# BlazeIt.net
KiCad netlist of a schematic drawn in EAGLE
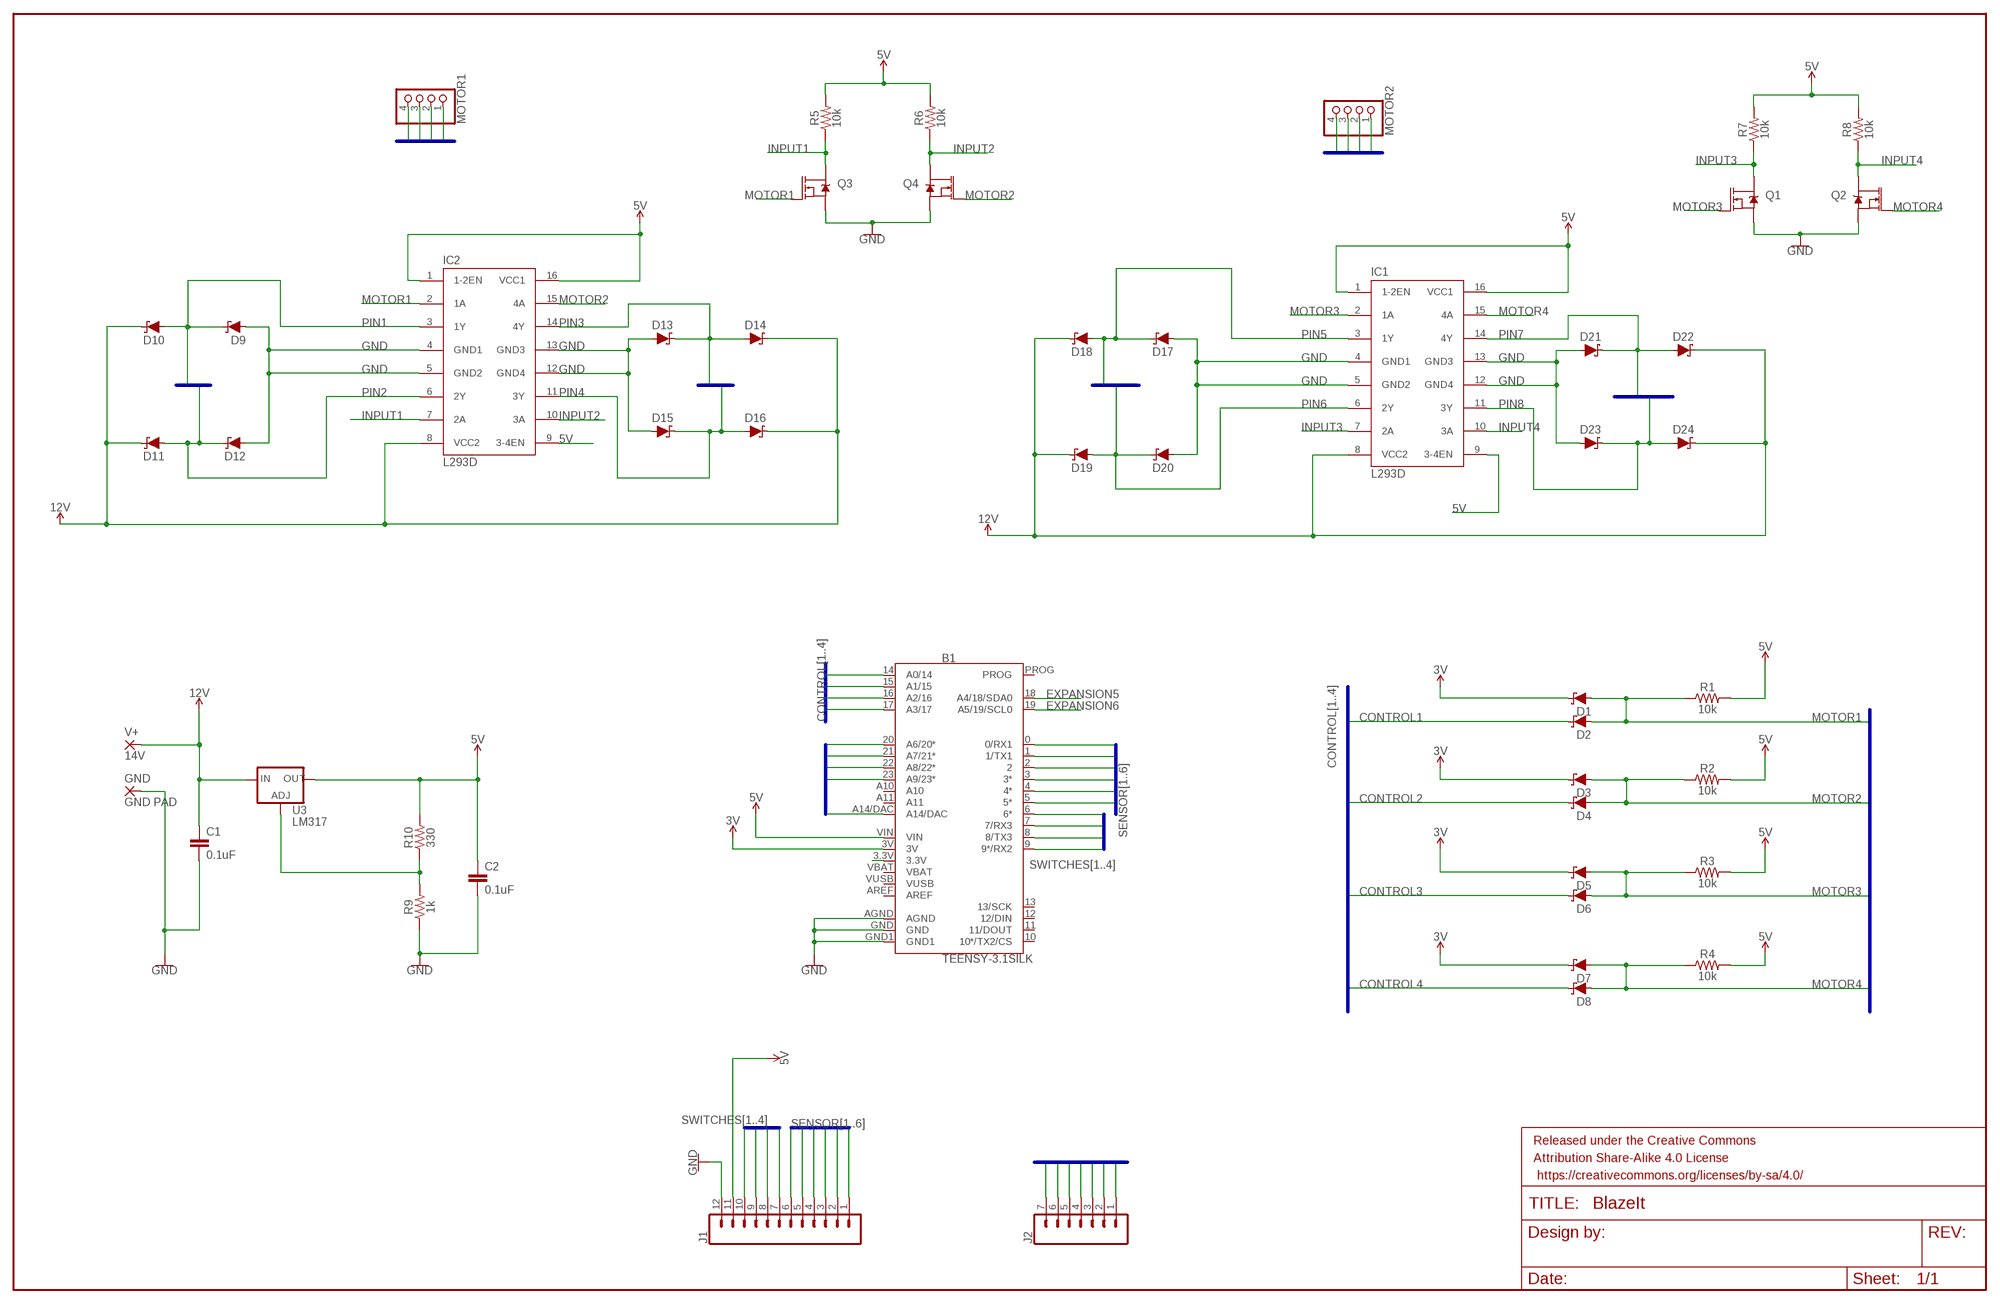
[diagram p0: schematic, sheet 1]

(export (version "E")
  (design (tool "Eeschema 10.0.6"))
  (components
    (comp (ref "B1")
      (value "TEENSY-3.1SILK")
      (footprint "eagle-import:TEENSY-3.1")
      (libsource (lib "eagle-import") (part "TEENSY-3.1SILK"))
    )
    (comp (ref "C1")
      (value "0.1uF")
      (footprint "eagle-import:0603")
      (libsource (lib "eagle-import") (part "0.1UF-0603-25V-5%"))
    )
    (comp (ref "C2")
      (value "0.1uF")
      (footprint "eagle-import:0603")
      (libsource (lib "eagle-import") (part "0.1UF-0603-25V-5%"))
    )
    (comp (ref "D1")
      (value "DIODE-SCHOTTKY-PMEG4005EJ")
      (footprint "eagle-import:SOD-323")
      (libsource (lib "eagle-import") (part "DIODE-SCHOTTKY-PMEG4005EJ"))
    )
    (comp (ref "D2")
      (value "DIODE-SCHOTTKY-PMEG4005EJ")
      (footprint "eagle-import:SOD-323")
      (libsource (lib "eagle-import") (part "DIODE-SCHOTTKY-PMEG4005EJ"))
    )
    (comp (ref "D3")
      (value "DIODE-SCHOTTKY-PMEG4005EJ")
      (footprint "eagle-import:SOD-323")
      (libsource (lib "eagle-import") (part "DIODE-SCHOTTKY-PMEG4005EJ"))
    )
    (comp (ref "D4")
      (value "DIODE-SCHOTTKY-PMEG4005EJ")
      (footprint "eagle-import:SOD-323")
      (libsource (lib "eagle-import") (part "DIODE-SCHOTTKY-PMEG4005EJ"))
    )
    (comp (ref "D5")
      (value "DIODE-SCHOTTKY-PMEG4005EJ")
      (footprint "eagle-import:SOD-323")
      (libsource (lib "eagle-import") (part "DIODE-SCHOTTKY-PMEG4005EJ"))
    )
    (comp (ref "D6")
      (value "DIODE-SCHOTTKY-PMEG4005EJ")
      (footprint "eagle-import:SOD-323")
      (libsource (lib "eagle-import") (part "DIODE-SCHOTTKY-PMEG4005EJ"))
    )
    (comp (ref "D7")
      (value "DIODE-SCHOTTKY-PMEG4005EJ")
      (footprint "eagle-import:SOD-323")
      (libsource (lib "eagle-import") (part "DIODE-SCHOTTKY-PMEG4005EJ"))
    )
    (comp (ref "D8")
      (value "DIODE-SCHOTTKY-PMEG4005EJ")
      (footprint "eagle-import:SOD-323")
      (libsource (lib "eagle-import") (part "DIODE-SCHOTTKY-PMEG4005EJ"))
    )
    (comp (ref "D9")
      (value "DIODE-SCHOTTKY-PMEG4005EJ")
      (footprint "eagle-import:SOD-323")
      (libsource (lib "eagle-import") (part "DIODE-SCHOTTKY-PMEG4005EJ"))
    )
    (comp (ref "D10")
      (value "DIODE-SCHOTTKY-PMEG4005EJ")
      (footprint "eagle-import:SOD-323")
      (libsource (lib "eagle-import") (part "DIODE-SCHOTTKY-PMEG4005EJ"))
    )
    (comp (ref "D11")
      (value "DIODE-SCHOTTKY-PMEG4005EJ")
      (footprint "eagle-import:SOD-323")
      (libsource (lib "eagle-import") (part "DIODE-SCHOTTKY-PMEG4005EJ"))
    )
    (comp (ref "D12")
      (value "DIODE-SCHOTTKY-PMEG4005EJ")
      (footprint "eagle-import:SOD-323")
      (libsource (lib "eagle-import") (part "DIODE-SCHOTTKY-PMEG4005EJ"))
    )
    (comp (ref "D13")
      (value "DIODE-SCHOTTKY-PMEG4005EJ")
      (footprint "eagle-import:SOD-323")
      (libsource (lib "eagle-import") (part "DIODE-SCHOTTKY-PMEG4005EJ"))
    )
    (comp (ref "D14")
      (value "DIODE-SCHOTTKY-PMEG4005EJ")
      (footprint "eagle-import:SOD-323")
      (libsource (lib "eagle-import") (part "DIODE-SCHOTTKY-PMEG4005EJ"))
    )
    (comp (ref "D15")
      (value "DIODE-SCHOTTKY-PMEG4005EJ")
      (footprint "eagle-import:SOD-323")
      (libsource (lib "eagle-import") (part "DIODE-SCHOTTKY-PMEG4005EJ"))
    )
    (comp (ref "D16")
      (value "DIODE-SCHOTTKY-PMEG4005EJ")
      (footprint "eagle-import:SOD-323")
      (libsource (lib "eagle-import") (part "DIODE-SCHOTTKY-PMEG4005EJ"))
    )
    (comp (ref "D17")
      (value "DIODE-SCHOTTKY-PMEG4005EJ")
      (footprint "eagle-import:SOD-323")
      (libsource (lib "eagle-import") (part "DIODE-SCHOTTKY-PMEG4005EJ"))
    )
    (comp (ref "D18")
      (value "DIODE-SCHOTTKY-PMEG4005EJ")
      (footprint "eagle-import:SOD-323")
      (libsource (lib "eagle-import") (part "DIODE-SCHOTTKY-PMEG4005EJ"))
    )
    (comp (ref "D19")
      (value "DIODE-SCHOTTKY-PMEG4005EJ")
      (footprint "eagle-import:SOD-323")
      (libsource (lib "eagle-import") (part "DIODE-SCHOTTKY-PMEG4005EJ"))
    )
    (comp (ref "D20")
      (value "DIODE-SCHOTTKY-PMEG4005EJ")
      (footprint "eagle-import:SOD-323")
      (libsource (lib "eagle-import") (part "DIODE-SCHOTTKY-PMEG4005EJ"))
    )
    (comp (ref "D21")
      (value "DIODE-SCHOTTKY-PMEG4005EJ")
      (footprint "eagle-import:SOD-323")
      (libsource (lib "eagle-import") (part "DIODE-SCHOTTKY-PMEG4005EJ"))
    )
    (comp (ref "D22")
      (value "DIODE-SCHOTTKY-PMEG4005EJ")
      (footprint "eagle-import:SOD-323")
      (libsource (lib "eagle-import") (part "DIODE-SCHOTTKY-PMEG4005EJ"))
    )
    (comp (ref "D23")
      (value "DIODE-SCHOTTKY-PMEG4005EJ")
      (footprint "eagle-import:SOD-323")
      (libsource (lib "eagle-import") (part "DIODE-SCHOTTKY-PMEG4005EJ"))
    )
    (comp (ref "D24")
      (value "DIODE-SCHOTTKY-PMEG4005EJ")
      (footprint "eagle-import:SOD-323")
      (libsource (lib "eagle-import") (part "DIODE-SCHOTTKY-PMEG4005EJ"))
    )
    (comp (ref "FRAME1")
      (value "FRAME-LEDGER")
      (footprint "eagle-import:CREATIVE_COMMONS")
      (libsource (lib "eagle-import") (part "FRAME-LEDGER"))
    )
    (comp (ref "GND")
      (value "GND PAD")
      (footprint "eagle-import:SMD2,54-5,08")
      (libsource (lib "eagle-import") (part "WIREPADSMD2,54-5,08"))
    )
    (comp (ref "IC1")
      (value "L293D")
      (footprint "eagle-import:DIL16")
      (libsource (lib "eagle-import") (part "L293D"))
    )
    (comp (ref "IC2")
      (value "L293D")
      (footprint "eagle-import:DIL16")
      (libsource (lib "eagle-import") (part "L293D"))
    )
    (comp (ref "J1")
      (value "CONN_12")
      (footprint "eagle-import:1X12")
      (libsource (lib "eagle-import") (part "CONN_12"))
    )
    (comp (ref "J2")
      (value "CONN_07LOCK")
      (footprint "eagle-import:1X07_LOCK")
      (libsource (lib "eagle-import") (part "CONN_07LOCK"))
    )
    (comp (ref "MOTOR1")
      (value "PINHD-1X4")
      (footprint "eagle-import:1X04")
      (libsource (lib "eagle-import") (part "PINHD-1X4"))
    )
    (comp (ref "MOTOR2")
      (value "PINHD-1X4")
      (footprint "eagle-import:1X04")
      (libsource (lib "eagle-import") (part "PINHD-1X4"))
    )
    (comp (ref "Q1")
      (value "MOSFET-NCH-2N7002PW")
      (footprint "eagle-import:SOT323")
      (libsource (lib "eagle-import") (part "MOSFET-NCH-2N7002PW"))
    )
    (comp (ref "Q2")
      (value "MOSFET-NCH-2N7002PW")
      (footprint "eagle-import:SOT323")
      (libsource (lib "eagle-import") (part "MOSFET-NCH-2N7002PW"))
    )
    (comp (ref "Q3")
      (value "MOSFET-NCH-2N7002PW")
      (footprint "eagle-import:SOT323")
      (libsource (lib "eagle-import") (part "MOSFET-NCH-2N7002PW"))
    )
    (comp (ref "Q4")
      (value "MOSFET-NCH-2N7002PW")
      (footprint "eagle-import:SOT323")
      (libsource (lib "eagle-import") (part "MOSFET-NCH-2N7002PW"))
    )
    (comp (ref "R1")
      (value "10k")
      (footprint "eagle-import:0603")
      (libsource (lib "eagle-import") (part "10KOHM-0603-1/10W-1%"))
    )
    (comp (ref "R2")
      (value "10k")
      (footprint "eagle-import:0603")
      (libsource (lib "eagle-import") (part "10KOHM-0603-1/10W-1%"))
    )
    (comp (ref "R3")
      (value "10k")
      (footprint "eagle-import:0603")
      (libsource (lib "eagle-import") (part "10KOHM-0603-1/10W-1%"))
    )
    (comp (ref "R4")
      (value "10k")
      (footprint "eagle-import:0603")
      (libsource (lib "eagle-import") (part "10KOHM-0603-1/10W-1%"))
    )
    (comp (ref "R5")
      (value "10k")
      (footprint "eagle-import:0603")
      (libsource (lib "eagle-import") (part "10KOHM-0603-1/10W-1%"))
    )
    (comp (ref "R6")
      (value "10k")
      (footprint "eagle-import:0603")
      (libsource (lib "eagle-import") (part "10KOHM-0603-1/10W-1%"))
    )
    (comp (ref "R7")
      (value "10k")
      (footprint "eagle-import:0603")
      (libsource (lib "eagle-import") (part "10KOHM-0603-1/10W-1%"))
    )
    (comp (ref "R8")
      (value "10k")
      (footprint "eagle-import:0603")
      (libsource (lib "eagle-import") (part "10KOHM-0603-1/10W-1%"))
    )
    (comp (ref "R9")
      (value "1k")
      (footprint "eagle-import:0603")
      (libsource (lib "eagle-import") (part "1KOHM-0603-1/10W-1%"))
    )
    (comp (ref "R10")
      (value "330")
      (footprint "eagle-import:0603")
      (libsource (lib "eagle-import") (part "3.3KOHM-0603-1/10W-1%"))
    )
    (comp (ref "U3")
      (value "LM317")
      (footprint "eagle-import:TO220-ADJ")
      (libsource (lib "eagle-import") (part "V_REG_317SINK"))
    )
    (comp (ref "V+")
      (value "14V")
      (footprint "eagle-import:SMD2,54-5,08")
      (libsource (lib "eagle-import") (part "WIREPADSMD2,54-5,08"))
    )
  )
  (nets
    (net (code "5") (name "3.3V") (class "Default")
      (node (ref "B1") (pin "3V") (pinfunction "3V_3V") (pintype "power_in"))
      (node (ref "D1") (pin "C") (pinfunction "C_C") (pintype "passive"))
      (node (ref "D3") (pin "C") (pinfunction "C_C") (pintype "passive"))
      (node (ref "D5") (pin "C") (pinfunction "C_C") (pintype "passive"))
      (node (ref "D7") (pin "C") (pinfunction "C_C") (pintype "passive"))
    )
    (net (code "6") (name "5V") (class "Default")
      (node (ref "B1") (pin "VIN") (pinfunction "VIN_VIN") (pintype "power_in"))
      (node (ref "C2") (pin "1") (pinfunction "1_1") (pintype "passive"))
      (node (ref "IC1") (pin "1") (pinfunction "1-2EN_1") (pintype "input"))
      (node (ref "IC1") (pin "16") (pinfunction "VCC1_16") (pintype "power_in"))
      (node (ref "IC1") (pin "9") (pinfunction "3-4EN_9") (pintype "input"))
      (node (ref "IC2") (pin "1") (pinfunction "1-2EN_1") (pintype "input"))
      (node (ref "IC2") (pin "16") (pinfunction "VCC1_16") (pintype "power_in"))
      (node (ref "IC2") (pin "9") (pinfunction "3-4EN_9") (pintype "input"))
      (node (ref "J1") (pin "11") (pinfunction "11_11") (pintype "passive"))
      (node (ref "R1") (pin "2") (pinfunction "2_2") (pintype "passive"))
      (node (ref "R10") (pin "2") (pinfunction "2_2") (pintype "passive"))
      (node (ref "R2") (pin "2") (pinfunction "2_2") (pintype "passive"))
      (node (ref "R3") (pin "2") (pinfunction "2_2") (pintype "passive"))
      (node (ref "R4") (pin "2") (pinfunction "2_2") (pintype "passive"))
      (node (ref "R5") (pin "2") (pinfunction "2_2") (pintype "passive"))
      (node (ref "R6") (pin "2") (pinfunction "2_2") (pintype "passive"))
      (node (ref "R7") (pin "2") (pinfunction "2_2") (pintype "passive"))
      (node (ref "R8") (pin "2") (pinfunction "2_2") (pintype "passive"))
      (node (ref "U3") (pin "OUT") (pinfunction "OUT_OUT") (pintype "output"))
    )
    (net (code "7") (name "12V") (class "Default")
      (node (ref "C1") (pin "1") (pinfunction "1_1") (pintype "passive"))
      (node (ref "D10") (pin "C") (pinfunction "C_C") (pintype "passive"))
      (node (ref "D11") (pin "C") (pinfunction "C_C") (pintype "passive"))
      (node (ref "D14") (pin "C") (pinfunction "C_C") (pintype "passive"))
      (node (ref "D16") (pin "C") (pinfunction "C_C") (pintype "passive"))
      (node (ref "D18") (pin "C") (pinfunction "C_C") (pintype "passive"))
      (node (ref "D19") (pin "C") (pinfunction "C_C") (pintype "passive"))
      (node (ref "D22") (pin "C") (pinfunction "C_C") (pintype "passive"))
      (node (ref "D24") (pin "C") (pinfunction "C_C") (pintype "passive"))
      (node (ref "IC1") (pin "8") (pinfunction "VCC2_8") (pintype "power_in"))
      (node (ref "IC2") (pin "8") (pinfunction "VCC2_8") (pintype "power_in"))
      (node (ref "U3") (pin "IN") (pinfunction "IN_IN") (pintype "input"))
      (node (ref "V+") (pin "1") (pinfunction "P_1") (pintype "passive"))
    )
    (net (code "8") (name "CONTROL1") (class "Default")
      (node (ref "B1") (pin "17") (pinfunction "A3/17_17") (pintype "bidirectional"))
      (node (ref "D2") (pin "C") (pinfunction "C_C") (pintype "passive"))
    )
    (net (code "9") (name "CONTROL2") (class "Default")
      (node (ref "B1") (pin "16") (pinfunction "A2/16_16") (pintype "bidirectional"))
      (node (ref "D4") (pin "C") (pinfunction "C_C") (pintype "passive"))
    )
    (net (code "10") (name "CONTROL3") (class "Default")
      (node (ref "B1") (pin "15") (pinfunction "A1/15_15") (pintype "bidirectional"))
      (node (ref "D6") (pin "C") (pinfunction "C_C") (pintype "passive"))
    )
    (net (code "11") (name "CONTROL4") (class "Default")
      (node (ref "B1") (pin "14") (pinfunction "A0/14_14") (pintype "bidirectional"))
      (node (ref "D8") (pin "C") (pinfunction "C_C") (pintype "passive"))
    )
    (net (code "12") (name "EXPANSION1") (class "Default")
      (node (ref "B1") (pin "20") (pinfunction "A6/20*_20") (pintype "bidirectional"))
      (node (ref "J2") (pin "1") (pinfunction "1_1") (pintype "passive"))
    )
    (net (code "13") (name "EXPANSION2") (class "Default")
      (node (ref "B1") (pin "21") (pinfunction "A7/21*_21") (pintype "bidirectional"))
      (node (ref "J2") (pin "2") (pinfunction "2_2") (pintype "passive"))
    )
    (net (code "14") (name "EXPANSION3") (class "Default")
      (node (ref "B1") (pin "22") (pinfunction "A8/22*_22") (pintype "bidirectional"))
      (node (ref "J2") (pin "3") (pinfunction "3_3") (pintype "passive"))
    )
    (net (code "15") (name "EXPANSION4") (class "Default")
      (node (ref "B1") (pin "23") (pinfunction "A9/23*_23") (pintype "bidirectional"))
      (node (ref "J2") (pin "4") (pinfunction "4_4") (pintype "passive"))
    )
    (net (code "16") (name "EXPANSION5") (class "Default")
      (node (ref "B1") (pin "18") (pinfunction "A4/18/SDA0_18") (pintype "bidirectional"))
      (node (ref "J2") (pin "5") (pinfunction "5_5") (pintype "passive"))
    )
    (net (code "17") (name "EXPANSION6") (class "Default")
      (node (ref "B1") (pin "19") (pinfunction "A5/19/SCL0_19") (pintype "bidirectional"))
      (node (ref "J2") (pin "6") (pinfunction "6_6") (pintype "passive"))
    )
    (net (code "18") (name "EXPANSION7") (class "Default")
      (node (ref "B1") (pin "A14/DAC") (pinfunction "A14/DAC_A14/DAC") (pintype "bidirectional"))
      (node (ref "J2") (pin "7") (pinfunction "7_7") (pintype "passive"))
    )
    (net (code "19") (name "GND") (class "Default")
      (node (ref "B1") (pin "AGND") (pinfunction "AGND_AGND") (pintype "power_in"))
      (node (ref "B1") (pin "GND") (pinfunction "GND_GND") (pintype "power_in"))
      (node (ref "B1") (pin "GND1") (pinfunction "GND1_GND1") (pintype "power_in"))
      (node (ref "C1") (pin "2") (pinfunction "2_2") (pintype "passive"))
      (node (ref "C2") (pin "2") (pinfunction "2_2") (pintype "passive"))
      (node (ref "D12") (pin "A") (pinfunction "A_A") (pintype "passive"))
      (node (ref "D13") (pin "A") (pinfunction "A_A") (pintype "passive"))
      (node (ref "D15") (pin "A") (pinfunction "A_A") (pintype "passive"))
      (node (ref "D17") (pin "A") (pinfunction "A_A") (pintype "passive"))
      (node (ref "D20") (pin "A") (pinfunction "A_A") (pintype "passive"))
      (node (ref "D21") (pin "A") (pinfunction "A_A") (pintype "passive"))
      (node (ref "D23") (pin "A") (pinfunction "A_A") (pintype "passive"))
      (node (ref "D9") (pin "A") (pinfunction "A_A") (pintype "passive"))
      (node (ref "GND") (pin "1") (pinfunction "P_1") (pintype "passive"))
      (node (ref "IC1") (pin "12") (pinfunction "GND4_12") (pintype "power_in"))
      (node (ref "IC1") (pin "13") (pinfunction "GND3_13") (pintype "power_in"))
      (node (ref "IC1") (pin "4") (pinfunction "GND1_4") (pintype "power_in"))
      (node (ref "IC1") (pin "5") (pinfunction "GND2_5") (pintype "power_in"))
      (node (ref "IC2") (pin "12") (pinfunction "GND4_12") (pintype "power_in"))
      (node (ref "IC2") (pin "13") (pinfunction "GND3_13") (pintype "power_in"))
      (node (ref "IC2") (pin "4") (pinfunction "GND1_4") (pintype "power_in"))
      (node (ref "IC2") (pin "5") (pinfunction "GND2_5") (pintype "power_in"))
      (node (ref "J1") (pin "12") (pinfunction "12_12") (pintype "passive"))
      (node (ref "Q1") (pin "2") (pinfunction "S_2") (pintype "bidirectional"))
      (node (ref "Q2") (pin "2") (pinfunction "S_2") (pintype "bidirectional"))
      (node (ref "Q3") (pin "2") (pinfunction "S_2") (pintype "bidirectional"))
      (node (ref "Q4") (pin "2") (pinfunction "S_2") (pintype "bidirectional"))
      (node (ref "R9") (pin "1") (pinfunction "1_1") (pintype "passive"))
    )
    (net (code "20") (name "INPUT1") (class "Default")
      (node (ref "IC2") (pin "7") (pinfunction "2A_7") (pintype "input"))
      (node (ref "Q3") (pin "3") (pinfunction "D_3") (pintype "bidirectional"))
      (node (ref "R5") (pin "1") (pinfunction "1_1") (pintype "passive"))
    )
    (net (code "21") (name "INPUT2") (class "Default")
      (node (ref "IC2") (pin "10") (pinfunction "3A_10") (pintype "input"))
      (node (ref "Q4") (pin "3") (pinfunction "D_3") (pintype "bidirectional"))
      (node (ref "R6") (pin "1") (pinfunction "1_1") (pintype "passive"))
    )
    (net (code "22") (name "INPUT3") (class "Default")
      (node (ref "IC1") (pin "7") (pinfunction "2A_7") (pintype "input"))
      (node (ref "Q1") (pin "3") (pinfunction "D_3") (pintype "bidirectional"))
      (node (ref "R7") (pin "1") (pinfunction "1_1") (pintype "passive"))
    )
    (net (code "23") (name "INPUT4") (class "Default")
      (node (ref "IC1") (pin "10") (pinfunction "3A_10") (pintype "input"))
      (node (ref "Q2") (pin "3") (pinfunction "D_3") (pintype "bidirectional"))
      (node (ref "R8") (pin "1") (pinfunction "1_1") (pintype "passive"))
    )
    (net (code "24") (name "MOTOR1") (class "Default")
      (node (ref "D1") (pin "A") (pinfunction "A_A") (pintype "passive"))
      (node (ref "D2") (pin "A") (pinfunction "A_A") (pintype "passive"))
      (node (ref "IC2") (pin "2") (pinfunction "1A_2") (pintype "input"))
      (node (ref "Q3") (pin "1") (pinfunction "G_1") (pintype "bidirectional"))
      (node (ref "R1") (pin "1") (pinfunction "1_1") (pintype "passive"))
    )
    (net (code "25") (name "MOTOR2") (class "Default")
      (node (ref "D3") (pin "A") (pinfunction "A_A") (pintype "passive"))
      (node (ref "D4") (pin "A") (pinfunction "A_A") (pintype "passive"))
      (node (ref "IC2") (pin "15") (pinfunction "4A_15") (pintype "input"))
      (node (ref "Q4") (pin "1") (pinfunction "G_1") (pintype "bidirectional"))
      (node (ref "R2") (pin "1") (pinfunction "1_1") (pintype "passive"))
    )
    (net (code "26") (name "MOTOR3") (class "Default")
      (node (ref "D5") (pin "A") (pinfunction "A_A") (pintype "passive"))
      (node (ref "D6") (pin "A") (pinfunction "A_A") (pintype "passive"))
      (node (ref "IC1") (pin "2") (pinfunction "1A_2") (pintype "input"))
      (node (ref "Q1") (pin "1") (pinfunction "G_1") (pintype "bidirectional"))
      (node (ref "R3") (pin "1") (pinfunction "1_1") (pintype "passive"))
    )
    (net (code "27") (name "MOTOR4") (class "Default")
      (node (ref "D7") (pin "A") (pinfunction "A_A") (pintype "passive"))
      (node (ref "D8") (pin "A") (pinfunction "A_A") (pintype "passive"))
      (node (ref "IC1") (pin "15") (pinfunction "4A_15") (pintype "input"))
      (node (ref "Q2") (pin "1") (pinfunction "G_1") (pintype "bidirectional"))
      (node (ref "R4") (pin "1") (pinfunction "1_1") (pintype "passive"))
    )
    (net (code "28") (name "Net-(R10-Pad1)") (class "Default")
      (node (ref "R10") (pin "1") (pinfunction "1_1") (pintype "passive"))
      (node (ref "R9") (pin "2") (pinfunction "2_2") (pintype "passive"))
      (node (ref "U3") (pin "ADJ") (pinfunction "ADJ_ADJ") (pintype "input"))
    )
    (net (code "29") (name "PIN1") (class "Default")
      (node (ref "D10") (pin "A") (pinfunction "A_A") (pintype "passive"))
      (node (ref "D9") (pin "C") (pinfunction "C_C") (pintype "passive"))
      (node (ref "IC2") (pin "3") (pinfunction "1Y_3") (pintype "output"))
      (node (ref "MOTOR1") (pin "4") (pinfunction "4_4") (pintype "passive"))
    )
    (net (code "30") (name "PIN2") (class "Default")
      (node (ref "D11") (pin "A") (pinfunction "A_A") (pintype "passive"))
      (node (ref "D12") (pin "C") (pinfunction "C_C") (pintype "passive"))
      (node (ref "IC2") (pin "6") (pinfunction "2Y_6") (pintype "output"))
      (node (ref "MOTOR1") (pin "3") (pinfunction "3_3") (pintype "passive"))
    )
    (net (code "31") (name "PIN3") (class "Default")
      (node (ref "D13") (pin "C") (pinfunction "C_C") (pintype "passive"))
      (node (ref "D14") (pin "A") (pinfunction "A_A") (pintype "passive"))
      (node (ref "IC2") (pin "14") (pinfunction "4Y_14") (pintype "output"))
      (node (ref "MOTOR1") (pin "2") (pinfunction "2_2") (pintype "passive"))
    )
    (net (code "32") (name "PIN4") (class "Default")
      (node (ref "D15") (pin "C") (pinfunction "C_C") (pintype "passive"))
      (node (ref "D16") (pin "A") (pinfunction "A_A") (pintype "passive"))
      (node (ref "IC2") (pin "11") (pinfunction "3Y_11") (pintype "output"))
      (node (ref "MOTOR1") (pin "1") (pinfunction "1_1") (pintype "passive"))
    )
    (net (code "33") (name "PIN5") (class "Default")
      (node (ref "D17") (pin "C") (pinfunction "C_C") (pintype "passive"))
      (node (ref "D18") (pin "A") (pinfunction "A_A") (pintype "passive"))
      (node (ref "IC1") (pin "3") (pinfunction "1Y_3") (pintype "output"))
      (node (ref "MOTOR2") (pin "4") (pinfunction "4_4") (pintype "passive"))
    )
    (net (code "34") (name "PIN6") (class "Default")
      (node (ref "D19") (pin "A") (pinfunction "A_A") (pintype "passive"))
      (node (ref "D20") (pin "C") (pinfunction "C_C") (pintype "passive"))
      (node (ref "IC1") (pin "6") (pinfunction "2Y_6") (pintype "output"))
      (node (ref "MOTOR2") (pin "3") (pinfunction "3_3") (pintype "passive"))
    )
    (net (code "35") (name "PIN7") (class "Default")
      (node (ref "D21") (pin "C") (pinfunction "C_C") (pintype "passive"))
      (node (ref "D22") (pin "A") (pinfunction "A_A") (pintype "passive"))
      (node (ref "IC1") (pin "14") (pinfunction "4Y_14") (pintype "output"))
      (node (ref "MOTOR2") (pin "2") (pinfunction "2_2") (pintype "passive"))
    )
    (net (code "36") (name "PIN8") (class "Default")
      (node (ref "D23") (pin "C") (pinfunction "C_C") (pintype "passive"))
      (node (ref "D24") (pin "A") (pinfunction "A_A") (pintype "passive"))
      (node (ref "IC1") (pin "11") (pinfunction "3Y_11") (pintype "output"))
      (node (ref "MOTOR2") (pin "1") (pinfunction "1_1") (pintype "passive"))
    )
    (net (code "37") (name "SENSOR1") (class "Default")
      (node (ref "B1") (pin "0") (pinfunction "0/RX1_0") (pintype "bidirectional"))
      (node (ref "J1") (pin "1") (pinfunction "1_1") (pintype "passive"))
    )
    (net (code "38") (name "SENSOR2") (class "Default")
      (node (ref "B1") (pin "1") (pinfunction "1/TX1_1") (pintype "bidirectional"))
      (node (ref "J1") (pin "2") (pinfunction "2_2") (pintype "passive"))
    )
    (net (code "39") (name "SENSOR3") (class "Default")
      (node (ref "B1") (pin "2") (pinfunction "2_2") (pintype "bidirectional"))
      (node (ref "J1") (pin "3") (pinfunction "3_3") (pintype "passive"))
    )
    (net (code "40") (name "SENSOR4") (class "Default")
      (node (ref "B1") (pin "3") (pinfunction "3*_3") (pintype "bidirectional"))
      (node (ref "J1") (pin "4") (pinfunction "4_4") (pintype "passive"))
    )
    (net (code "41") (name "SENSOR5") (class "Default")
      (node (ref "B1") (pin "4") (pinfunction "4*_4") (pintype "bidirectional"))
      (node (ref "J1") (pin "5") (pinfunction "5_5") (pintype "passive"))
    )
    (net (code "42") (name "SENSOR6") (class "Default")
      (node (ref "B1") (pin "5") (pinfunction "5*_5") (pintype "bidirectional"))
      (node (ref "J1") (pin "6") (pinfunction "6_6") (pintype "passive"))
    )
    (net (code "43") (name "SWITCHES1") (class "Default")
      (node (ref "B1") (pin "6") (pinfunction "6*_6") (pintype "bidirectional"))
      (node (ref "J1") (pin "7") (pinfunction "7_7") (pintype "passive"))
    )
    (net (code "44") (name "SWITCHES2") (class "Default")
      (node (ref "B1") (pin "7") (pinfunction "7/RX3_7") (pintype "bidirectional"))
      (node (ref "J1") (pin "8") (pinfunction "8_8") (pintype "passive"))
    )
    (net (code "45") (name "SWITCHES3") (class "Default")
      (node (ref "B1") (pin "8") (pinfunction "8/TX3_8") (pintype "bidirectional"))
      (node (ref "J1") (pin "9") (pinfunction "9_9") (pintype "passive"))
    )
    (net (code "46") (name "SWITCHES4") (class "Default")
      (node (ref "B1") (pin "9") (pinfunction "9*/RX2_9") (pintype "bidirectional"))
      (node (ref "J1") (pin "10") (pinfunction "10_10") (pintype "passive"))
    )
    (net (code "47") (name "VBAT") (class "Default")
      (node (ref "B1") (pin "VBAT") (pinfunction "VBAT_VBAT") (pintype "power_in"))
    )
    (net (code "48") (name "VUSB") (class "Default")
      (node (ref "B1") (pin "VUSB") (pinfunction "VUSB_VUSB") (pintype "power_in"))
    )
    (net (code "49") (name "unconnected-(B1-10*{slash}TX2{slash}CS-Pad10)") (class "Default")
      (node (ref "B1") (pin "10") (pinfunction "10*/TX2/CS_10") (pintype "bidirectional"))
    )
    (net (code "50") (name "unconnected-(B1-11{slash}DOUT-Pad11)") (class "Default")
      (node (ref "B1") (pin "11") (pinfunction "11/DOUT_11") (pintype "bidirectional"))
    )
    (net (code "51") (name "unconnected-(B1-12{slash}DIN-Pad12)") (class "Default")
      (node (ref "B1") (pin "12") (pinfunction "12/DIN_12") (pintype "bidirectional"))
    )
    (net (code "52") (name "unconnected-(B1-13{slash}SCK-Pad13)") (class "Default")
      (node (ref "B1") (pin "13") (pinfunction "13/SCK_13") (pintype "bidirectional"))
    )
    (net (code "53") (name "unconnected-(B1-Pad3.3V)") (class "Default")
      (node (ref "B1") (pin "3.3V") (pinfunction "3.3V_3.3V") (pintype "power_in"))
    )
    (net (code "54") (name "unconnected-(B1-PadA10)") (class "Default")
      (node (ref "B1") (pin "A10") (pinfunction "A10_A10") (pintype "bidirectional"))
    )
    (net (code "55") (name "unconnected-(B1-PadA11)") (class "Default")
      (node (ref "B1") (pin "A11") (pinfunction "A11_A11") (pintype "bidirectional"))
    )
    (net (code "56") (name "unconnected-(B1-PadAREF)") (class "Default")
      (node (ref "B1") (pin "AREF") (pinfunction "AREF_AREF") (pintype "bidirectional"))
    )
    (net (code "57") (name "unconnected-(B1-PadPROG)") (class "Default")
      (node (ref "B1") (pin "PROG") (pinfunction "PROG_PROG") (pintype "bidirectional"))
    )
  )
)
